# EchoHelloBoard2.net
KiCad netlist of a schematic drawn in EAGLE
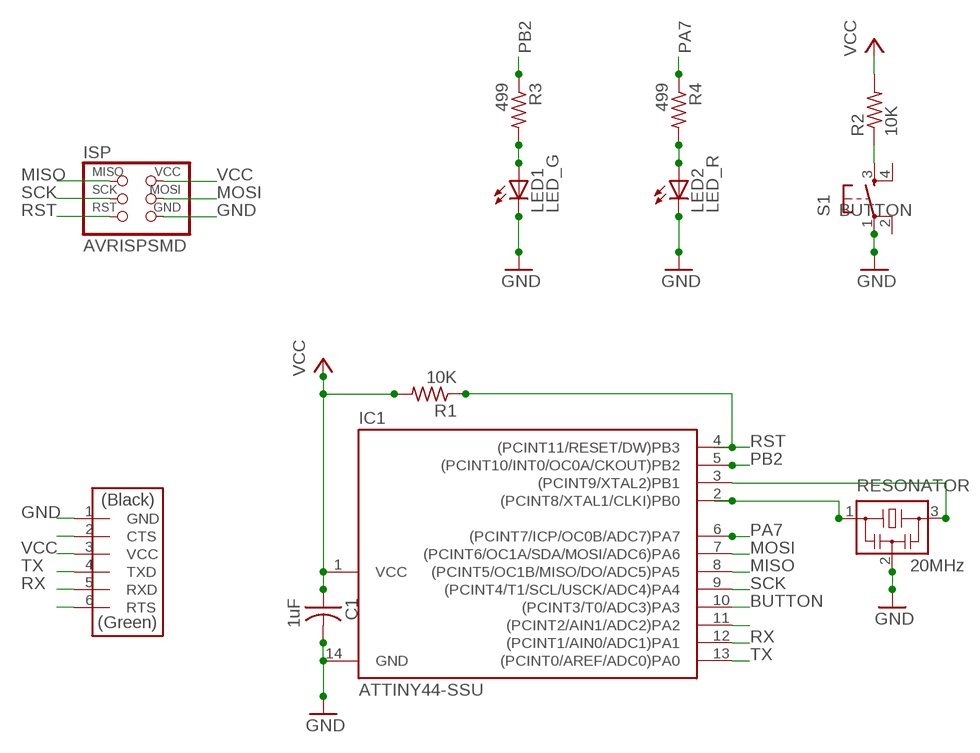
[diagram p0: schematic, sheet 1]

(export (version "E")
  (design (tool "Eeschema 10.0.6"))
  (components
    (comp (ref "C1")
      (value "1uF")
      (footprint "eagle-import:C1206FAB")
      (libsource (lib "eagle-import") (part "CAP-US1206FAB"))
    )
    (comp (ref "IC1")
      (value "ATTINY44-SSU")
      (footprint "eagle-import:SOIC14")
      (libsource (lib "eagle-import") (part "ATTINY44-SSU"))
    )
    (comp (ref "ISP")
      (value "AVRISPSMD")
      (footprint "eagle-import:2X03SMD")
      (libsource (lib "eagle-import") (part "AVRISPSMD"))
    )
    (comp (ref "LED1")
      (value "LED_G")
      (footprint "eagle-import:LED1206FAB")
      (libsource (lib "eagle-import") (part "LEDFAB1206"))
    )
    (comp (ref "LED2")
      (value "LED_R")
      (footprint "eagle-import:LED1206FAB")
      (libsource (lib "eagle-import") (part "LEDFAB1206"))
    )
    (comp (ref "R1")
      (value "10K")
      (footprint "eagle-import:R1206FAB")
      (libsource (lib "eagle-import") (part "RES-US1206FAB"))
    )
    (comp (ref "R2")
      (value "10K")
      (footprint "eagle-import:R1206FAB")
      (libsource (lib "eagle-import") (part "RES-US1206FAB"))
    )
    (comp (ref "R3")
      (value "499")
      (footprint "eagle-import:R1206FAB")
      (libsource (lib "eagle-import") (part "RES-US1206FAB"))
    )
    (comp (ref "R4")
      (value "499")
      (footprint "eagle-import:R1206FAB")
      (libsource (lib "eagle-import") (part "RES-US1206FAB"))
    )
    (comp (ref "RESONATOR")
      (value "20MHz")
      (footprint "eagle-import:EFOBM")
      (libsource (lib "eagle-import") (part "RESONATOR"))
    )
    (comp (ref "S1")
      (value "6MM_SWITCH6MM_SWITCH")
      (footprint "eagle-import:6MM_SWITCH")
      (libsource (lib "eagle-import") (part "6MM_SWITCH6MM_SWITCH"))
    )
    (comp (ref "U$2")
      (value "FTDI-SMD-HEADER")
      (footprint "eagle-import:1X06SMD")
      (libsource (lib "eagle-import") (part "FTDI-SMD-HEADER"))
    )
  )
  (nets
    (net (code "1") (name "/BUTTON") (class "Default")
      (node (ref "IC1") (pin "10") (pinfunction "(PCINT3/T0/ADC3)PA3_10") (pintype "bidirectional"))
      (node (ref "R2") (pin "1") (pinfunction "1_1") (pintype "passive"))
      (node (ref "S1") (pin "3") (pinfunction "S_3") (pintype "passive"))
    )
    (net (code "2") (name "/MISO") (class "Default")
      (node (ref "IC1") (pin "8") (pinfunction "(PCINT5/OC1B/MISO/DO/ADC5)PA5_8") (pintype "bidirectional"))
      (node (ref "ISP") (pin "1") (pinfunction "MISO_1") (pintype "passive"))
    )
    (net (code "3") (name "/MOSI") (class "Default")
      (node (ref "IC1") (pin "7") (pinfunction "(PCINT6/OC1A/SDA/MOSI/ADC6)PA6_7") (pintype "bidirectional"))
      (node (ref "ISP") (pin "4") (pinfunction "MOSI_4") (pintype "passive"))
    )
    (net (code "4") (name "/PA7") (class "Default")
      (node (ref "IC1") (pin "6") (pinfunction "(PCINT7/ICP/OC0B/ADC7)PA7_6") (pintype "bidirectional"))
      (node (ref "R4") (pin "1") (pinfunction "1_1") (pintype "passive"))
    )
    (net (code "5") (name "/PB2") (class "Default")
      (node (ref "IC1") (pin "5") (pinfunction "(PCINT10/INT0/OC0A/CKOUT)PB2_5") (pintype "bidirectional"))
      (node (ref "R3") (pin "1") (pinfunction "1_1") (pintype "passive"))
    )
    (net (code "6") (name "/RST") (class "Default")
      (node (ref "IC1") (pin "4") (pinfunction "(PCINT11/RESET/DW)PB3_4") (pintype "bidirectional"))
      (node (ref "ISP") (pin "5") (pinfunction "RST_5") (pintype "passive"))
      (node (ref "R1") (pin "1") (pinfunction "1_1") (pintype "passive"))
    )
    (net (code "7") (name "/RX") (class "Default")
      (node (ref "IC1") (pin "12") (pinfunction "(PCINT1/AIN0/ADC1)PA1_12") (pintype "bidirectional"))
      (node (ref "U$2") (pin "5") (pinfunction "RXD_5") (pintype "bidirectional"))
    )
    (net (code "8") (name "/SCK") (class "Default")
      (node (ref "IC1") (pin "9") (pinfunction "(PCINT4/T1/SCL/USCK/ADC4)PA4_9") (pintype "bidirectional"))
      (node (ref "ISP") (pin "3") (pinfunction "SCK_3") (pintype "passive"))
    )
    (net (code "9") (name "/TX") (class "Default")
      (node (ref "IC1") (pin "13") (pinfunction "(PCINT0/AREF/ADC0)PA0_13") (pintype "bidirectional"))
      (node (ref "U$2") (pin "4") (pinfunction "TXD_4") (pintype "bidirectional"))
    )
    (net (code "10") (name "GND") (class "Default")
      (node (ref "C1") (pin "2") (pinfunction "2_2") (pintype "passive"))
      (node (ref "IC1") (pin "14") (pinfunction "GND_14") (pintype "power_in"))
      (node (ref "ISP") (pin "6") (pinfunction "GND_6") (pintype "passive"))
      (node (ref "LED1") (pin "2") (pinfunction "C_2") (pintype "passive"))
      (node (ref "LED2") (pin "2") (pinfunction "C_2") (pintype "passive"))
      (node (ref "RESONATOR") (pin "2") (pinfunction "2_2") (pintype "passive"))
      (node (ref "S1") (pin "1") (pinfunction "P_1") (pintype "passive"))
      (node (ref "U$2") (pin "1") (pinfunction "GND_1") (pintype "bidirectional"))
    )
    (net (code "11") (name "Net-(IC1-(PCINT8{slash}XTAL1{slash}CLKI)PB0)") (class "Default")
      (node (ref "IC1") (pin "2") (pinfunction "(PCINT8/XTAL1/CLKI)PB0_2") (pintype "bidirectional"))
      (node (ref "RESONATOR") (pin "1") (pinfunction "1_1") (pintype "passive"))
    )
    (net (code "12") (name "Net-(IC1-(PCINT9{slash}XTAL2)PB1)") (class "Default")
      (node (ref "IC1") (pin "3") (pinfunction "(PCINT9/XTAL2)PB1_3") (pintype "bidirectional"))
      (node (ref "RESONATOR") (pin "3") (pinfunction "3_3") (pintype "passive"))
    )
    (net (code "13") (name "Net-(LED1-A)") (class "Default")
      (node (ref "LED1") (pin "1") (pinfunction "A_1") (pintype "passive"))
      (node (ref "R3") (pin "2") (pinfunction "2_2") (pintype "passive"))
    )
    (net (code "14") (name "Net-(LED2-A)") (class "Default")
      (node (ref "LED2") (pin "1") (pinfunction "A_1") (pintype "passive"))
      (node (ref "R4") (pin "2") (pinfunction "2_2") (pintype "passive"))
    )
    (net (code "15") (name "VCC") (class "Default")
      (node (ref "C1") (pin "1") (pinfunction "1_1") (pintype "passive"))
      (node (ref "IC1") (pin "1") (pinfunction "VCC_1") (pintype "power_in"))
      (node (ref "ISP") (pin "2") (pinfunction "VCC_2") (pintype "passive"))
      (node (ref "R1") (pin "2") (pinfunction "2_2") (pintype "passive"))
      (node (ref "R2") (pin "2") (pinfunction "2_2") (pintype "passive"))
      (node (ref "U$2") (pin "3") (pinfunction "VCC_3") (pintype "bidirectional"))
    )
    (net (code "16") (name "unconnected-(IC1-(PCINT2{slash}AIN1{slash}ADC2)PA2-Pad11)") (class "Default")
      (node (ref "IC1") (pin "11") (pinfunction "(PCINT2/AIN1/ADC2)PA2_11") (pintype "bidirectional"))
    )
    (net (code "17") (name "unconnected-(S1-P1-Pad2)") (class "Default")
      (node (ref "S1") (pin "2") (pinfunction "P1_2") (pintype "passive"))
    )
    (net (code "18") (name "unconnected-(S1-S1-Pad4)") (class "Default")
      (node (ref "S1") (pin "4") (pinfunction "S1_4") (pintype "passive"))
    )
    (net (code "19") (name "unconnected-(U$2-CTS-Pad2)") (class "Default")
      (node (ref "U$2") (pin "2") (pinfunction "CTS_2") (pintype "bidirectional"))
    )
    (net (code "20") (name "unconnected-(U$2-RTS-Pad6)") (class "Default")
      (node (ref "U$2") (pin "6") (pinfunction "RTS_6") (pintype "bidirectional"))
    )
  )
)
